# MLP_ESPControlBoard_Rev_1.net
KiCad netlist of a schematic drawn in EAGLE
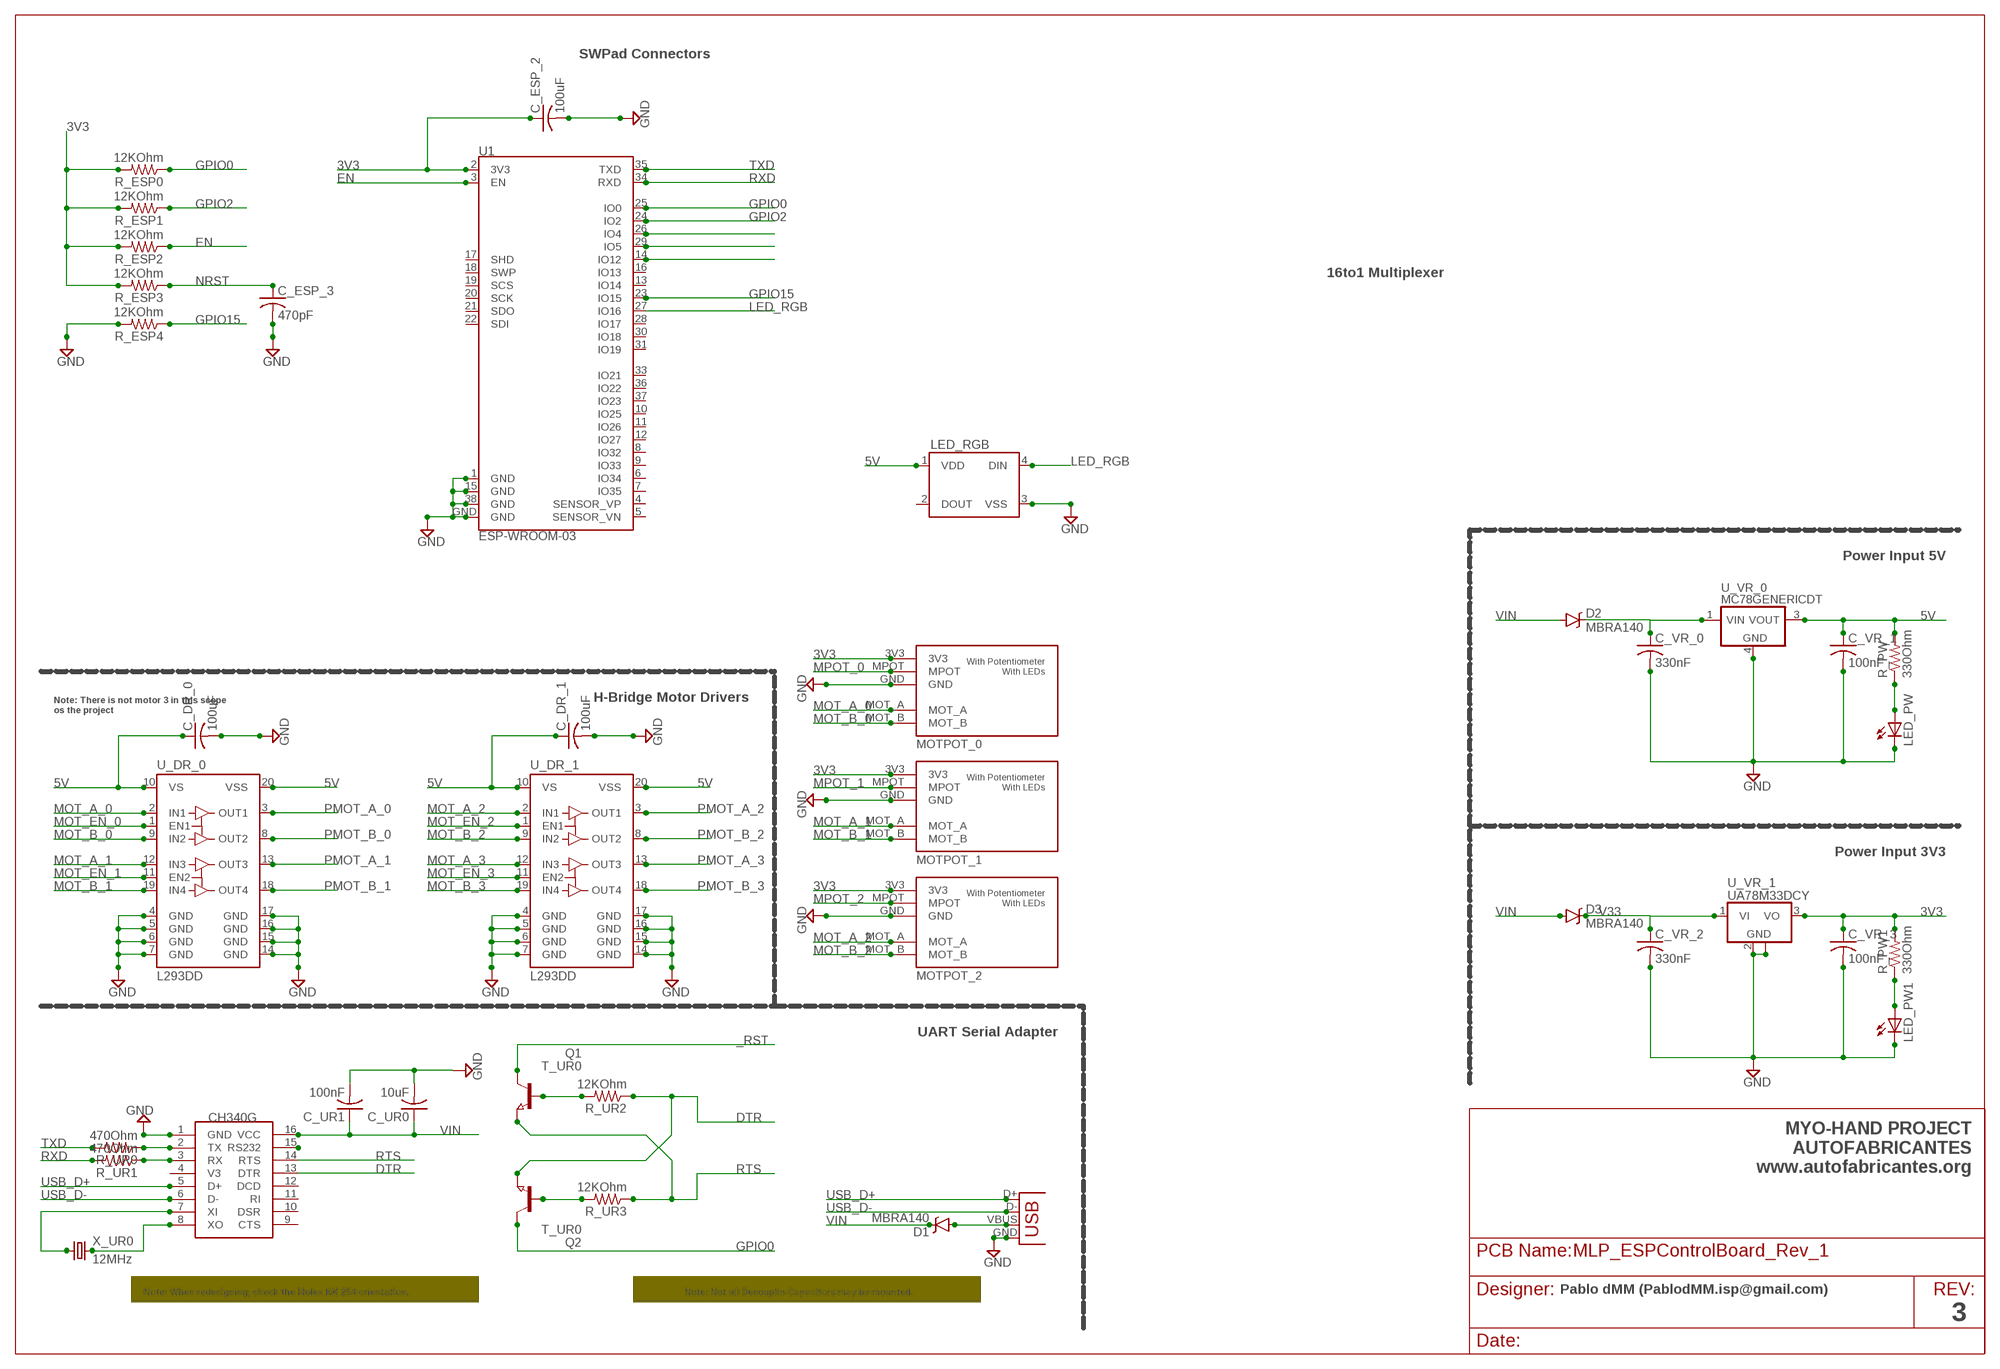
[diagram p0: schematic, sheet 1]

(export (version "E")
  (design (tool "Eeschema 10.0.6"))
  (components
    (comp (ref "C_DR_0")
      (value "100uF")
      (footprint "eagle-import:C0805K")
      (libsource (lib "eagle-import") (part "C-USC0805K"))
    )
    (comp (ref "C_DR_1")
      (value "100uF")
      (footprint "eagle-import:C0805K")
      (libsource (lib "eagle-import") (part "C-USC0805K"))
    )
    (comp (ref "C_ESP_2")
      (value "100uF")
      (footprint "eagle-import:C0805K")
      (libsource (lib "eagle-import") (part "C-USC0805K"))
    )
    (comp (ref "C_ESP_3")
      (value "470pF")
      (footprint "eagle-import:C0805K")
      (libsource (lib "eagle-import") (part "C-USC0805K"))
    )
    (comp (ref "C_UR0")
      (value "10uF")
      (footprint "eagle-import:C0805K")
      (libsource (lib "eagle-import") (part "C-USC0805K"))
    )
    (comp (ref "C_UR1")
      (value "100nF")
      (footprint "eagle-import:C0805K")
      (libsource (lib "eagle-import") (part "C-USC0805K"))
    )
    (comp (ref "C_VR_0")
      (value "330nF")
      (footprint "eagle-import:C1206K")
      (libsource (lib "eagle-import") (part "C-USC1206K"))
    )
    (comp (ref "C_VR_1")
      (value "100nF")
      (footprint "eagle-import:C1206K")
      (libsource (lib "eagle-import") (part "C-USC1206K"))
    )
    (comp (ref "C_VR_2")
      (value "330nF")
      (footprint "eagle-import:C1206K")
      (libsource (lib "eagle-import") (part "C-USC1206K"))
    )
    (comp (ref "C_VR_3")
      (value "100nF")
      (footprint "eagle-import:C1206K")
      (libsource (lib "eagle-import") (part "C-USC1206K"))
    )
    (comp (ref "D1")
      (value "MBRA140")
      (footprint "eagle-import:SMA-DIODE")
      (libsource (lib "eagle-import") (part "MBRA140"))
    )
    (comp (ref "D2")
      (value "MBRA140")
      (footprint "eagle-import:SMA-DIODE")
      (libsource (lib "eagle-import") (part "MBRA140"))
    )
    (comp (ref "D3")
      (value "MBRA140")
      (footprint "eagle-import:SMA-DIODE")
      (libsource (lib "eagle-import") (part "MBRA140"))
    )
    (comp (ref "LED_PW")
      (value "LEDSMT1206")
      (footprint "eagle-import:1206")
      (libsource (lib "eagle-import") (part "LEDSMT1206"))
    )
    (comp (ref "LED_PW1")
      (value "LEDSMT1206")
      (footprint "eagle-import:1206")
      (libsource (lib "eagle-import") (part "LEDSMT1206"))
    )
    (comp (ref "LED_RGB")
      (value "WS2812B")
      (footprint "eagle-import:WS2812B")
      (libsource (lib "eagle-import") (part "WS2812B"))
    )
    (comp (ref "MOTPOT_0")
      (value "POLOLU_MOT_POT")
      (footprint "eagle-import:POLOLU_MOT_POT")
      (libsource (lib "eagle-import") (part "POLOLU_MOT_POT"))
    )
    (comp (ref "MOTPOT_1")
      (value "POLOLU_MOT_POT")
      (footprint "eagle-import:POLOLU_MOT_POT")
      (libsource (lib "eagle-import") (part "POLOLU_MOT_POT"))
    )
    (comp (ref "MOTPOT_2")
      (value "POLOLU_MOT_POT")
      (footprint "eagle-import:POLOLU_MOT_POT")
      (libsource (lib "eagle-import") (part "POLOLU_MOT_POT"))
    )
    (comp (ref "Q1")
      (value "T_UR0")
      (footprint "eagle-import:SOT23")
      (libsource (lib "eagle-import") (part "NPN-TRANSISTOR_SOT23"))
    )
    (comp (ref "Q2")
      (value "T_UR0")
      (footprint "eagle-import:SOT23")
      (libsource (lib "eagle-import") (part "NPN-TRANSISTOR_SOT23"))
    )
    (comp (ref "R_ESP0")
      (value "12KOhm")
      (footprint "eagle-import:M0805")
      (libsource (lib "eagle-import") (part "R-US_M0805"))
    )
    (comp (ref "R_ESP1")
      (value "12KOhm")
      (footprint "eagle-import:M0805")
      (libsource (lib "eagle-import") (part "R-US_M0805"))
    )
    (comp (ref "R_ESP2")
      (value "12KOhm")
      (footprint "eagle-import:M0805")
      (libsource (lib "eagle-import") (part "R-US_M0805"))
    )
    (comp (ref "R_ESP3")
      (value "12KOhm")
      (footprint "eagle-import:M0805")
      (libsource (lib "eagle-import") (part "R-US_M0805"))
    )
    (comp (ref "R_ESP4")
      (value "12KOhm")
      (footprint "eagle-import:M0805")
      (libsource (lib "eagle-import") (part "R-US_M0805"))
    )
    (comp (ref "R_PW")
      (value "330Ohm")
      (footprint "eagle-import:M1206")
      (libsource (lib "eagle-import") (part "R-US_M1206"))
    )
    (comp (ref "R_PW1")
      (value "330Ohm")
      (footprint "eagle-import:M1206")
      (libsource (lib "eagle-import") (part "R-US_M1206"))
    )
    (comp (ref "R_UR0")
      (value "470Ohm")
      (footprint "eagle-import:M1206")
      (libsource (lib "eagle-import") (part "R-US_M1206"))
    )
    (comp (ref "R_UR1")
      (value "470Ohm")
      (footprint "eagle-import:M1206")
      (libsource (lib "eagle-import") (part "R-US_M1206"))
    )
    (comp (ref "R_UR2")
      (value "12KOhm")
      (footprint "eagle-import:M1206")
      (libsource (lib "eagle-import") (part "R-US_M1206"))
    )
    (comp (ref "R_UR3")
      (value "12KOhm")
      (footprint "eagle-import:M1206")
      (libsource (lib "eagle-import") (part "R-US_M1206"))
    )
    (comp (ref "U1")
      (value "ESP-WROOM-03")
      (footprint "eagle-import:ESP-WROOM-03")
      (libsource (lib "eagle-import") (part "ESP-WROOM-03"))
    )
    (comp (ref "U_DR_0")
      (value "L293DD")
      (footprint "eagle-import:SO20")
      (libsource (lib "eagle-import") (part "L293DD"))
    )
    (comp (ref "U_DR_1")
      (value "L293DD")
      (footprint "eagle-import:SO20")
      (libsource (lib "eagle-import") (part "L293DD"))
    )
    (comp (ref "U_UR0")
      (value "CH340G")
      (footprint "eagle-import:SOIC16")
      (libsource (lib "eagle-import") (part "CH340G"))
    )
    (comp (ref "U_VR_0")
      (value "MC78GENERICDT")
      (footprint "eagle-import:DPAK-3")
      (libsource (lib "eagle-import") (part "MC78DTGENERIC"))
    )
    (comp (ref "U_VR_1")
      (value "UA78M33DCY")
      (footprint "eagle-import:SOT223")
      (libsource (lib "eagle-import") (part "UA78MDCY33"))
    )
    (comp (ref "X1")
      (value "USB-MICROB")
      (footprint "eagle-import:USB-MICROB")
      (libsource (lib "eagle-import") (part "USB-MICROB"))
    )
    (comp (ref "X_UR0")
      (value "12MHz")
      (footprint "eagle-import:CTS406")
      (libsource (lib "eagle-import") (part "CRYSTALCTS406"))
    )
  )
  (nets
    (net (code "1") (name "/3V3") (class "Default")
      (node (ref "C_ESP_2") (pin "1") (pinfunction "1_1") (pintype "passive"))
      (node (ref "C_VR_3") (pin "1") (pinfunction "1_1") (pintype "passive"))
      (node (ref "MOTPOT_0") (pin "3V3") (pinfunction "3V3_3V3") (pintype "bidirectional"))
      (node (ref "MOTPOT_1") (pin "3V3") (pinfunction "3V3_3V3") (pintype "bidirectional"))
      (node (ref "MOTPOT_2") (pin "3V3") (pinfunction "3V3_3V3") (pintype "bidirectional"))
      (node (ref "R_ESP0") (pin "2") (pinfunction "2_2") (pintype "passive"))
      (node (ref "R_ESP1") (pin "2") (pinfunction "2_2") (pintype "passive"))
      (node (ref "R_ESP2") (pin "2") (pinfunction "2_2") (pintype "passive"))
      (node (ref "R_ESP3") (pin "2") (pinfunction "2_2") (pintype "passive"))
      (node (ref "R_PW1") (pin "2") (pinfunction "2_2") (pintype "passive"))
      (node (ref "U1") (pin "2") (pinfunction "3V3_2") (pintype "bidirectional"))
      (node (ref "U_VR_1") (pin "3") (pinfunction "VO_3") (pintype "passive"))
    )
    (net (code "2") (name "/5V") (class "Default")
      (node (ref "C_DR_0") (pin "1") (pinfunction "1_1") (pintype "passive"))
      (node (ref "C_DR_1") (pin "1") (pinfunction "1_1") (pintype "passive"))
      (node (ref "C_VR_1") (pin "1") (pinfunction "1_1") (pintype "passive"))
      (node (ref "LED_RGB") (pin "1") (pinfunction "VDD_1") (pintype "power_in"))
      (node (ref "R_PW") (pin "2") (pinfunction "2_2") (pintype "passive"))
      (node (ref "U_DR_0") (pin "10") (pinfunction "VS_10") (pintype "power_in"))
      (node (ref "U_DR_0") (pin "20") (pinfunction "VSS_20") (pintype "power_in"))
      (node (ref "U_DR_1") (pin "10") (pinfunction "VS_10") (pintype "power_in"))
      (node (ref "U_DR_1") (pin "20") (pinfunction "VSS_20") (pintype "power_in"))
      (node (ref "U_VR_0") (pin "3") (pinfunction "VOUT_3") (pintype "power_in"))
    )
    (net (code "3") (name "/DTR") (class "Default")
      (node (ref "Q2") (pin "2") (pinfunction "E_2") (pintype "passive"))
      (node (ref "R_UR2") (pin "1") (pinfunction "1_1") (pintype "passive"))
      (node (ref "U_UR0") (pin "13") (pinfunction "DTR_13") (pintype "bidirectional"))
    )
    (net (code "4") (name "/EN") (class "Default")
      (node (ref "R_ESP2") (pin "1") (pinfunction "1_1") (pintype "passive"))
      (node (ref "U1") (pin "3") (pinfunction "EN_3") (pintype "bidirectional"))
    )
    (net (code "5") (name "/GPIO0") (class "Default")
      (node (ref "Q2") (pin "3") (pinfunction "C_3") (pintype "passive"))
      (node (ref "R_ESP0") (pin "1") (pinfunction "1_1") (pintype "passive"))
      (node (ref "U1") (pin "25") (pinfunction "IO0_25") (pintype "bidirectional"))
    )
    (net (code "6") (name "/GPIO2") (class "Default")
      (node (ref "R_ESP1") (pin "1") (pinfunction "1_1") (pintype "passive"))
      (node (ref "U1") (pin "24") (pinfunction "IO2_24") (pintype "bidirectional"))
    )
    (net (code "7") (name "/GPIO15") (class "Default")
      (node (ref "R_ESP4") (pin "1") (pinfunction "1_1") (pintype "passive"))
      (node (ref "U1") (pin "23") (pinfunction "IO15_23") (pintype "bidirectional"))
    )
    (net (code "8") (name "/LED_RGB") (class "Default")
      (node (ref "LED_RGB") (pin "4") (pinfunction "DIN_4") (pintype "input"))
      (node (ref "U1") (pin "27") (pinfunction "IO16_27") (pintype "bidirectional"))
    )
    (net (code "9") (name "/MOT_A_0") (class "Default")
      (node (ref "MOTPOT_0") (pin "MOT_A") (pinfunction "MOT_A_MOT_A") (pintype "bidirectional"))
      (node (ref "U_DR_0") (pin "2") (pinfunction "IN1_2") (pintype "input"))
    )
    (net (code "10") (name "/MOT_A_1") (class "Default")
      (node (ref "MOTPOT_1") (pin "MOT_A") (pinfunction "MOT_A_MOT_A") (pintype "bidirectional"))
      (node (ref "U_DR_0") (pin "12") (pinfunction "IN3_12") (pintype "input"))
    )
    (net (code "11") (name "/MOT_A_2") (class "Default")
      (node (ref "MOTPOT_2") (pin "MOT_A") (pinfunction "MOT_A_MOT_A") (pintype "bidirectional"))
      (node (ref "U_DR_1") (pin "2") (pinfunction "IN1_2") (pintype "input"))
    )
    (net (code "12") (name "/MOT_A_3") (class "Default")
      (node (ref "U_DR_1") (pin "12") (pinfunction "IN3_12") (pintype "input"))
    )
    (net (code "13") (name "/MOT_B_0") (class "Default")
      (node (ref "MOTPOT_0") (pin "MOT_B") (pinfunction "MOT_B_MOT_B") (pintype "bidirectional"))
      (node (ref "U_DR_0") (pin "9") (pinfunction "IN2_9") (pintype "input"))
    )
    (net (code "14") (name "/MOT_B_1") (class "Default")
      (node (ref "MOTPOT_1") (pin "MOT_B") (pinfunction "MOT_B_MOT_B") (pintype "bidirectional"))
      (node (ref "U_DR_0") (pin "19") (pinfunction "IN4_19") (pintype "input"))
    )
    (net (code "15") (name "/MOT_B_2") (class "Default")
      (node (ref "MOTPOT_2") (pin "MOT_B") (pinfunction "MOT_B_MOT_B") (pintype "bidirectional"))
      (node (ref "U_DR_1") (pin "9") (pinfunction "IN2_9") (pintype "input"))
    )
    (net (code "16") (name "/MOT_B_3") (class "Default")
      (node (ref "U_DR_1") (pin "19") (pinfunction "IN4_19") (pintype "input"))
    )
    (net (code "17") (name "/MOT_EN_0") (class "Default")
      (node (ref "U_DR_0") (pin "1") (pinfunction "EN1_1") (pintype "input"))
    )
    (net (code "18") (name "/MOT_EN_1") (class "Default")
      (node (ref "U_DR_0") (pin "11") (pinfunction "EN2_11") (pintype "input"))
    )
    (net (code "19") (name "/MOT_EN_2") (class "Default")
      (node (ref "U_DR_1") (pin "1") (pinfunction "EN1_1") (pintype "input"))
    )
    (net (code "20") (name "/MOT_EN_3") (class "Default")
      (node (ref "U_DR_1") (pin "11") (pinfunction "EN2_11") (pintype "input"))
    )
    (net (code "21") (name "/MPOT_0") (class "Default")
      (node (ref "MOTPOT_0") (pin "MPOT") (pinfunction "MPOT_MPOT") (pintype "bidirectional"))
    )
    (net (code "22") (name "/MPOT_1") (class "Default")
      (node (ref "MOTPOT_1") (pin "MPOT") (pinfunction "MPOT_MPOT") (pintype "bidirectional"))
    )
    (net (code "23") (name "/MPOT_2") (class "Default")
      (node (ref "MOTPOT_2") (pin "MPOT") (pinfunction "MPOT_MPOT") (pintype "bidirectional"))
    )
    (net (code "24") (name "/NRST") (class "Default")
      (node (ref "C_ESP_3") (pin "1") (pinfunction "1_1") (pintype "passive"))
      (node (ref "R_ESP3") (pin "1") (pinfunction "1_1") (pintype "passive"))
    )
    (net (code "25") (name "/PMOT_A_0") (class "Default")
      (node (ref "U_DR_0") (pin "3") (pinfunction "OUT1_3") (pintype "output"))
    )
    (net (code "26") (name "/PMOT_A_1") (class "Default")
      (node (ref "U_DR_0") (pin "13") (pinfunction "OUT3_13") (pintype "output"))
    )
    (net (code "27") (name "/PMOT_A_2") (class "Default")
      (node (ref "U_DR_1") (pin "3") (pinfunction "OUT1_3") (pintype "output"))
    )
    (net (code "28") (name "/PMOT_A_3") (class "Default")
      (node (ref "U_DR_1") (pin "13") (pinfunction "OUT3_13") (pintype "output"))
    )
    (net (code "29") (name "/PMOT_B_0") (class "Default")
      (node (ref "U_DR_0") (pin "8") (pinfunction "OUT2_8") (pintype "output"))
    )
    (net (code "30") (name "/PMOT_B_1") (class "Default")
      (node (ref "U_DR_0") (pin "18") (pinfunction "OUT4_18") (pintype "output"))
    )
    (net (code "31") (name "/PMOT_B_2") (class "Default")
      (node (ref "U_DR_1") (pin "8") (pinfunction "OUT2_8") (pintype "output"))
    )
    (net (code "32") (name "/PMOT_B_3") (class "Default")
      (node (ref "U_DR_1") (pin "18") (pinfunction "OUT4_18") (pintype "output"))
    )
    (net (code "33") (name "/RTS") (class "Default")
      (node (ref "Q1") (pin "2") (pinfunction "E_2") (pintype "passive"))
      (node (ref "R_UR3") (pin "1") (pinfunction "1_1") (pintype "passive"))
      (node (ref "U_UR0") (pin "14") (pinfunction "RTS_14") (pintype "bidirectional"))
    )
    (net (code "34") (name "/RXD") (class "Default")
      (node (ref "R_UR1") (pin "2") (pinfunction "2_2") (pintype "passive"))
      (node (ref "U1") (pin "34") (pinfunction "RXD_34") (pintype "bidirectional"))
    )
    (net (code "35") (name "/TXD") (class "Default")
      (node (ref "R_UR0") (pin "2") (pinfunction "2_2") (pintype "passive"))
      (node (ref "U1") (pin "35") (pinfunction "TXD_35") (pintype "bidirectional"))
    )
    (net (code "36") (name "/USB_D+") (class "Default")
      (node (ref "U_UR0") (pin "5") (pinfunction "D+_5") (pintype "bidirectional"))
      (node (ref "X1") (pin "D+") (pinfunction "D+_D+") (pintype "bidirectional"))
    )
    (net (code "37") (name "/USB_D-") (class "Default")
      (node (ref "U_UR0") (pin "6") (pinfunction "D-_6") (pintype "bidirectional"))
      (node (ref "X1") (pin "D-") (pinfunction "D-_D-") (pintype "bidirectional"))
    )
    (net (code "38") (name "/V33") (class "Default")
      (node (ref "C_VR_2") (pin "1") (pinfunction "1_1") (pintype "passive"))
      (node (ref "D3") (pin "C") (pinfunction "C_C") (pintype "passive"))
      (node (ref "U_VR_1") (pin "1") (pinfunction "VI_1") (pintype "input"))
    )
    (net (code "39") (name "/VIN") (class "Default")
      (node (ref "C_UR0") (pin "1") (pinfunction "1_1") (pintype "passive"))
      (node (ref "C_UR1") (pin "1") (pinfunction "1_1") (pintype "passive"))
      (node (ref "D1") (pin "C") (pinfunction "C_C") (pintype "passive"))
      (node (ref "D2") (pin "A") (pinfunction "A_A") (pintype "passive"))
      (node (ref "D3") (pin "A") (pinfunction "A_A") (pintype "passive"))
      (node (ref "U_UR0") (pin "16") (pinfunction "VCC_16") (pintype "bidirectional"))
    )
    (net (code "40") (name "/_RST") (class "Default")
      (node (ref "Q1") (pin "3") (pinfunction "C_3") (pintype "passive"))
    )
    (net (code "41") (name "GND") (class "Default")
      (node (ref "C_DR_0") (pin "2") (pinfunction "2_2") (pintype "passive"))
      (node (ref "C_DR_1") (pin "2") (pinfunction "2_2") (pintype "passive"))
      (node (ref "C_ESP_2") (pin "2") (pinfunction "2_2") (pintype "passive"))
      (node (ref "C_ESP_3") (pin "2") (pinfunction "2_2") (pintype "passive"))
      (node (ref "C_UR0") (pin "2") (pinfunction "2_2") (pintype "passive"))
      (node (ref "C_UR1") (pin "2") (pinfunction "2_2") (pintype "passive"))
      (node (ref "C_VR_0") (pin "2") (pinfunction "2_2") (pintype "passive"))
      (node (ref "C_VR_1") (pin "2") (pinfunction "2_2") (pintype "passive"))
      (node (ref "C_VR_2") (pin "2") (pinfunction "2_2") (pintype "passive"))
      (node (ref "C_VR_3") (pin "2") (pinfunction "2_2") (pintype "passive"))
      (node (ref "LED_PW") (pin "C") (pinfunction "C_C") (pintype "passive"))
      (node (ref "LED_PW1") (pin "C") (pinfunction "C_C") (pintype "passive"))
      (node (ref "LED_RGB") (pin "3") (pinfunction "VSS_3") (pintype "power_in"))
      (node (ref "MOTPOT_0") (pin "GND") (pinfunction "GND_GND") (pintype "bidirectional"))
      (node (ref "MOTPOT_1") (pin "GND") (pinfunction "GND_GND") (pintype "bidirectional"))
      (node (ref "MOTPOT_2") (pin "GND") (pinfunction "GND_GND") (pintype "bidirectional"))
      (node (ref "R_ESP4") (pin "2") (pinfunction "2_2") (pintype "passive"))
      (node (ref "U1") (pin "1") (pinfunction "GND_1") (pintype "bidirectional"))
      (node (ref "U1") (pin "15") (pinfunction "GND_15") (pintype "bidirectional"))
      (node (ref "U1") (pin "38") (pinfunction "GND_38") (pintype "bidirectional"))
      (node (ref "U1") (pin "GND") (pinfunction "GND_GND") (pintype "bidirectional"))
      (node (ref "U_DR_0") (pin "14") (pinfunction "GND_14") (pintype "power_in"))
      (node (ref "U_DR_0") (pin "15") (pinfunction "GND_15") (pintype "power_in"))
      (node (ref "U_DR_0") (pin "16") (pinfunction "GND_16") (pintype "power_in"))
      (node (ref "U_DR_0") (pin "17") (pinfunction "GND_17") (pintype "power_in"))
      (node (ref "U_DR_0") (pin "4") (pinfunction "GND_4") (pintype "power_in"))
      (node (ref "U_DR_0") (pin "5") (pinfunction "GND_5") (pintype "power_in"))
      (node (ref "U_DR_0") (pin "6") (pinfunction "GND_6") (pintype "power_in"))
      (node (ref "U_DR_0") (pin "7") (pinfunction "GND_7") (pintype "power_in"))
      (node (ref "U_DR_1") (pin "14") (pinfunction "GND_14") (pintype "power_in"))
      (node (ref "U_DR_1") (pin "15") (pinfunction "GND_15") (pintype "power_in"))
      (node (ref "U_DR_1") (pin "16") (pinfunction "GND_16") (pintype "power_in"))
      (node (ref "U_DR_1") (pin "17") (pinfunction "GND_17") (pintype "power_in"))
      (node (ref "U_DR_1") (pin "4") (pinfunction "GND_4") (pintype "power_in"))
      (node (ref "U_DR_1") (pin "5") (pinfunction "GND_5") (pintype "power_in"))
      (node (ref "U_DR_1") (pin "6") (pinfunction "GND_6") (pintype "power_in"))
      (node (ref "U_DR_1") (pin "7") (pinfunction "GND_7") (pintype "power_in"))
      (node (ref "U_UR0") (pin "1") (pinfunction "GND_1") (pintype "bidirectional"))
      (node (ref "U_VR_0") (pin "4") (pinfunction "GND_4") (pintype "power_in"))
      (node (ref "U_VR_1") (pin "2") (pinfunction "GND_2") (pintype "passive"))
      (node (ref "U_VR_1") (pin "4") (pinfunction "GND_4") (pintype "passive"))
      (node (ref "X1") (pin "GND") (pinfunction "GND_GND") (pintype "bidirectional"))
    )
    (net (code "42") (name "Net-(D1-PadA)") (class "Default")
      (node (ref "D1") (pin "A") (pinfunction "A_A") (pintype "passive"))
      (node (ref "X1") (pin "VBUS") (pinfunction "VBUS_VBUS") (pintype "bidirectional"))
    )
    (net (code "43") (name "Net-(LED_PW-PadA)") (class "Default")
      (node (ref "LED_PW") (pin "A") (pinfunction "A_A") (pintype "passive"))
      (node (ref "R_PW") (pin "1") (pinfunction "1_1") (pintype "passive"))
    )
    (net (code "44") (name "Net-(LED_PW1-PadA)") (class "Default")
      (node (ref "LED_PW1") (pin "A") (pinfunction "A_A") (pintype "passive"))
      (node (ref "R_PW1") (pin "1") (pinfunction "1_1") (pintype "passive"))
    )
    (net (code "45") (name "Net-(Q1-B)") (class "Default")
      (node (ref "Q1") (pin "1") (pinfunction "B_1") (pintype "passive"))
      (node (ref "R_UR2") (pin "2") (pinfunction "2_2") (pintype "passive"))
    )
    (net (code "46") (name "Net-(Q2-B)") (class "Default")
      (node (ref "Q2") (pin "1") (pinfunction "B_1") (pintype "passive"))
      (node (ref "R_UR3") (pin "2") (pinfunction "2_2") (pintype "passive"))
    )
    (net (code "47") (name "Net-(U_UR0-RX)") (class "Default")
      (node (ref "R_UR1") (pin "1") (pinfunction "1_1") (pintype "passive"))
      (node (ref "U_UR0") (pin "3") (pinfunction "RX_3") (pintype "bidirectional"))
    )
    (net (code "48") (name "Net-(U_UR0-TX)") (class "Default")
      (node (ref "R_UR0") (pin "1") (pinfunction "1_1") (pintype "passive"))
      (node (ref "U_UR0") (pin "2") (pinfunction "TX_2") (pintype "bidirectional"))
    )
    (net (code "49") (name "Net-(U_UR0-XI)") (class "Default")
      (node (ref "U_UR0") (pin "7") (pinfunction "XI_7") (pintype "bidirectional"))
      (node (ref "X_UR0") (pin "1") (pinfunction "1_1") (pintype "passive"))
    )
    (net (code "50") (name "Net-(U_UR0-XO)") (class "Default")
      (node (ref "U_UR0") (pin "8") (pinfunction "XO_8") (pintype "bidirectional"))
      (node (ref "X_UR0") (pin "3") (pinfunction "2_3") (pintype "passive"))
    )
    (net (code "51") (name "Net-(U_VR_0-VIN)") (class "Default")
      (node (ref "C_VR_0") (pin "1") (pinfunction "1_1") (pintype "passive"))
      (node (ref "D2") (pin "C") (pinfunction "C_C") (pintype "passive"))
      (node (ref "U_VR_0") (pin "1") (pinfunction "VIN_1") (pintype "power_in"))
    )
    (net (code "52") (name "unconnected-(LED_RGB-DOUT-Pad2)") (class "Default")
      (node (ref "LED_RGB") (pin "2") (pinfunction "DOUT_2") (pintype "output"))
    )
    (net (code "53") (name "unconnected-(U1-IO4-Pad26)") (class "Default")
      (node (ref "U1") (pin "26") (pinfunction "IO4_26") (pintype "bidirectional"))
    )
    (net (code "54") (name "unconnected-(U1-IO5-Pad29)") (class "Default")
      (node (ref "U1") (pin "29") (pinfunction "IO5_29") (pintype "bidirectional"))
    )
    (net (code "55") (name "unconnected-(U1-IO12-Pad14)") (class "Default")
      (node (ref "U1") (pin "14") (pinfunction "IO12_14") (pintype "bidirectional"))
    )
    (net (code "56") (name "unconnected-(U1-IO13-Pad16)") (class "Default")
      (node (ref "U1") (pin "16") (pinfunction "IO13_16") (pintype "bidirectional"))
    )
    (net (code "57") (name "unconnected-(U1-IO14-Pad13)") (class "Default")
      (node (ref "U1") (pin "13") (pinfunction "IO14_13") (pintype "bidirectional"))
    )
    (net (code "58") (name "unconnected-(U1-IO17-Pad28)") (class "Default")
      (node (ref "U1") (pin "28") (pinfunction "IO17_28") (pintype "bidirectional"))
    )
    (net (code "59") (name "unconnected-(U1-IO18-Pad30)") (class "Default")
      (node (ref "U1") (pin "30") (pinfunction "IO18_30") (pintype "bidirectional"))
    )
    (net (code "60") (name "unconnected-(U1-IO19-Pad31)") (class "Default")
      (node (ref "U1") (pin "31") (pinfunction "IO19_31") (pintype "bidirectional"))
    )
    (net (code "61") (name "unconnected-(U1-IO21-Pad33)") (class "Default")
      (node (ref "U1") (pin "33") (pinfunction "IO21_33") (pintype "bidirectional"))
    )
    (net (code "62") (name "unconnected-(U1-IO22-Pad36)") (class "Default")
      (node (ref "U1") (pin "36") (pinfunction "IO22_36") (pintype "bidirectional"))
    )
    (net (code "63") (name "unconnected-(U1-IO23-Pad37)") (class "Default")
      (node (ref "U1") (pin "37") (pinfunction "IO23_37") (pintype "bidirectional"))
    )
    (net (code "64") (name "unconnected-(U1-IO25-Pad10)") (class "Default")
      (node (ref "U1") (pin "10") (pinfunction "IO25_10") (pintype "bidirectional"))
    )
    (net (code "65") (name "unconnected-(U1-IO26-Pad11)") (class "Default")
      (node (ref "U1") (pin "11") (pinfunction "IO26_11") (pintype "bidirectional"))
    )
    (net (code "66") (name "unconnected-(U1-IO27-Pad12)") (class "Default")
      (node (ref "U1") (pin "12") (pinfunction "IO27_12") (pintype "bidirectional"))
    )
    (net (code "67") (name "unconnected-(U1-IO32-Pad8)") (class "Default")
      (node (ref "U1") (pin "8") (pinfunction "IO32_8") (pintype "bidirectional"))
    )
    (net (code "68") (name "unconnected-(U1-IO33-Pad9)") (class "Default")
      (node (ref "U1") (pin "9") (pinfunction "IO33_9") (pintype "bidirectional"))
    )
    (net (code "69") (name "unconnected-(U1-IO34-Pad6)") (class "Default")
      (node (ref "U1") (pin "6") (pinfunction "IO34_6") (pintype "bidirectional"))
    )
    (net (code "70") (name "unconnected-(U1-IO35-Pad7)") (class "Default")
      (node (ref "U1") (pin "7") (pinfunction "IO35_7") (pintype "bidirectional"))
    )
    (net (code "71") (name "unconnected-(U1-SCK-Pad20)") (class "Default")
      (node (ref "U1") (pin "20") (pinfunction "SCK_20") (pintype "bidirectional"))
    )
    (net (code "72") (name "unconnected-(U1-SCS-Pad19)") (class "Default")
      (node (ref "U1") (pin "19") (pinfunction "SCS_19") (pintype "bidirectional"))
    )
    (net (code "73") (name "unconnected-(U1-SDI-Pad22)") (class "Default")
      (node (ref "U1") (pin "22") (pinfunction "SDI_22") (pintype "bidirectional"))
    )
    (net (code "74") (name "unconnected-(U1-SDO-Pad21)") (class "Default")
      (node (ref "U1") (pin "21") (pinfunction "SDO_21") (pintype "bidirectional"))
    )
    (net (code "75") (name "unconnected-(U1-SENSOR_VN-Pad5)") (class "Default")
      (node (ref "U1") (pin "5") (pinfunction "SENSOR_VN_5") (pintype "bidirectional"))
    )
    (net (code "76") (name "unconnected-(U1-SENSOR_VP-Pad4)") (class "Default")
      (node (ref "U1") (pin "4") (pinfunction "SENSOR_VP_4") (pintype "bidirectional"))
    )
    (net (code "77") (name "unconnected-(U1-SHD-Pad17)") (class "Default")
      (node (ref "U1") (pin "17") (pinfunction "SHD_17") (pintype "bidirectional"))
    )
    (net (code "78") (name "unconnected-(U1-SWP-Pad18)") (class "Default")
      (node (ref "U1") (pin "18") (pinfunction "SWP_18") (pintype "bidirectional"))
    )
    (net (code "79") (name "unconnected-(U_UR0-CTS-Pad9)") (class "Default")
      (node (ref "U_UR0") (pin "9") (pinfunction "CTS_9") (pintype "bidirectional"))
    )
    (net (code "80") (name "unconnected-(U_UR0-DCD-Pad12)") (class "Default")
      (node (ref "U_UR0") (pin "12") (pinfunction "DCD_12") (pintype "bidirectional"))
    )
    (net (code "81") (name "unconnected-(U_UR0-DSR-Pad10)") (class "Default")
      (node (ref "U_UR0") (pin "10") (pinfunction "DSR_10") (pintype "bidirectional"))
    )
    (net (code "82") (name "unconnected-(U_UR0-RI-Pad11)") (class "Default")
      (node (ref "U_UR0") (pin "11") (pinfunction "RI_11") (pintype "bidirectional"))
    )
    (net (code "83") (name "unconnected-(U_UR0-RS232-Pad15)") (class "Default")
      (node (ref "U_UR0") (pin "15") (pinfunction "RS232_15") (pintype "bidirectional"))
    )
    (net (code "84") (name "unconnected-(U_UR0-V3-Pad4)") (class "Default")
      (node (ref "U_UR0") (pin "4") (pinfunction "V3_4") (pintype "bidirectional"))
    )
  )
)
